# air_cylinder_control.net
KiCad netlist of a schematic drawn in Altium Designer
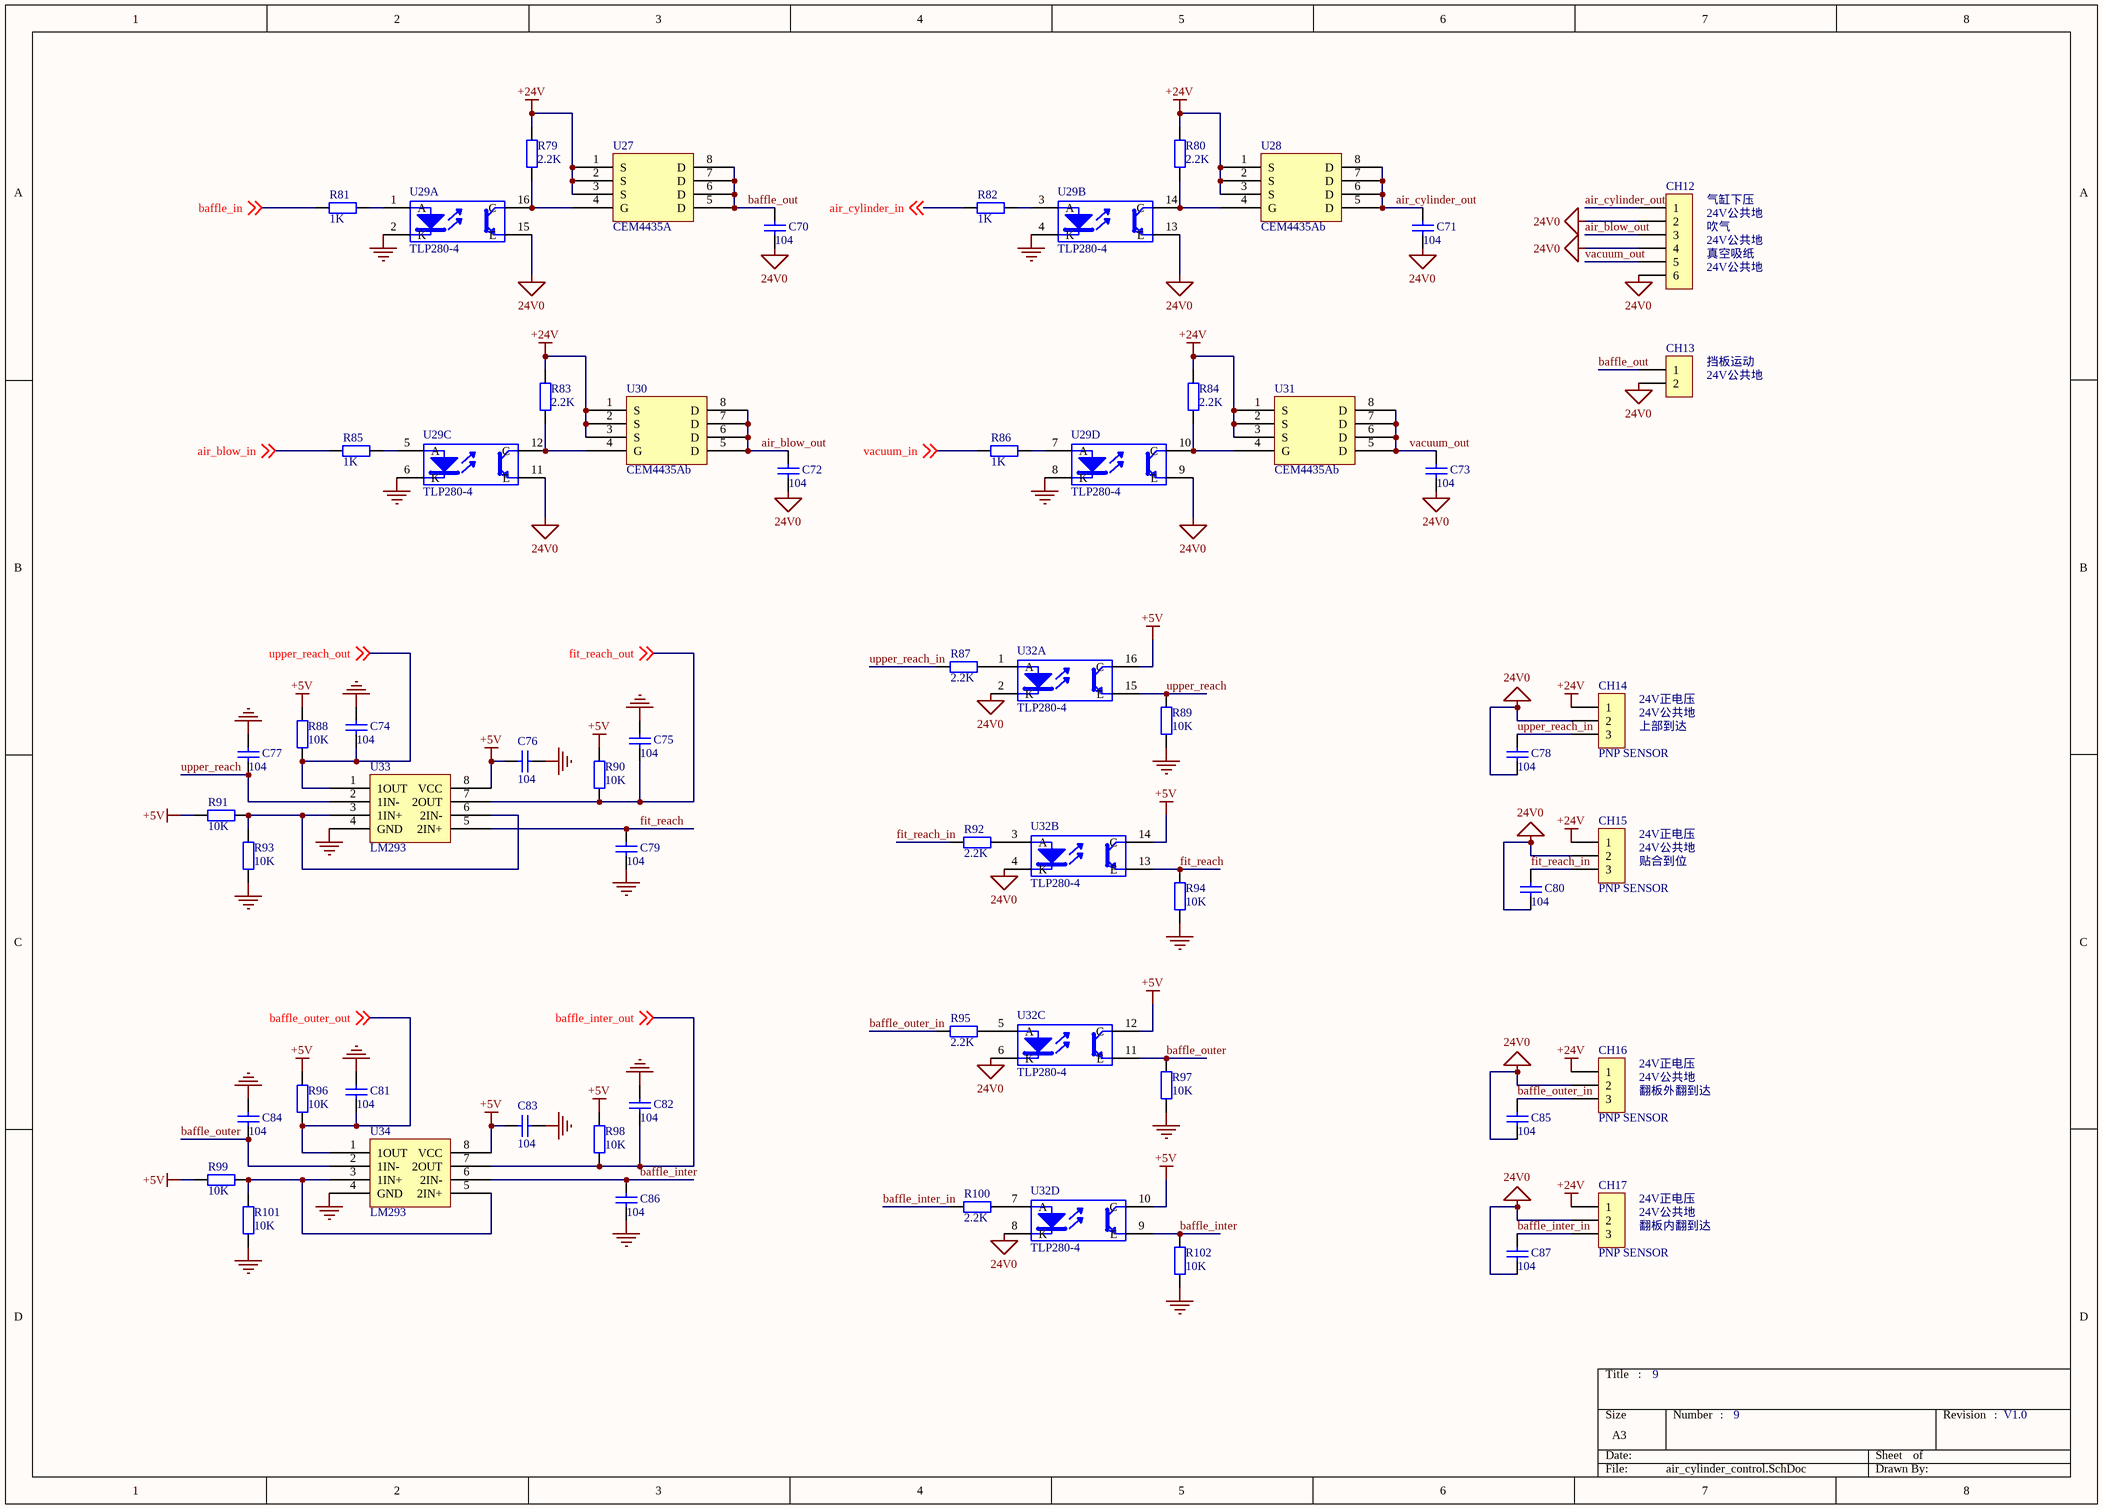
[diagram p0: air_cylinder_control.SchDoc]

(export (version "E")
  (design (tool "Eeschema 10.0.6"))
  (components
    (comp (ref "C70")
      (value "104")
      (footprint "0805")
      (description "Capacitor")
      (fields (field (name "Comment") "Capb") (field (name "PUBLISHER") "Altium Limited"))
      (libsource (lib "Miscellaneous Devices") (part "Cap"))
    )
    (comp (ref "C71")
      (value "104")
      (footprint "0805")
      (description "Capacitor")
      (fields (field (name "Comment") "Capb") (field (name "PUBLISHER") "Altium Limited"))
      (libsource (lib "Miscellaneous Devices") (part "Cap"))
    )
    (comp (ref "C72")
      (value "104")
      (footprint "0805")
      (description "Capacitor")
      (fields (field (name "Comment") "Capb") (field (name "PUBLISHER") "Altium Limited"))
      (libsource (lib "Miscellaneous Devices") (part "Cap"))
    )
    (comp (ref "C73")
      (value "104")
      (footprint "0805")
      (description "Capacitor")
      (fields (field (name "Comment") "Capb") (field (name "PUBLISHER") "Altium Limited"))
      (libsource (lib "Miscellaneous Devices") (part "Cap"))
    )
    (comp (ref "C74")
      (value "104")
      (footprint "0805")
      (description "Capacitor")
      (fields (field (name "Comment") "Cap") (field (name "PUBLISHER") "Altium Limited"))
      (libsource (lib "Miscellaneous Devices") (part "Cap"))
    )
    (comp (ref "C75")
      (value "104")
      (footprint "0805")
      (description "Capacitor")
      (fields (field (name "Comment") "Cap") (field (name "PUBLISHER") "Altium Limited"))
      (libsource (lib "Miscellaneous Devices") (part "Cap"))
    )
    (comp (ref "C76")
      (value "104")
      (footprint "0805")
      (description "Capacitor")
      (fields (field (name "Comment") "Cap") (field (name "PUBLISHER") "Altium Limited"))
      (libsource (lib "Miscellaneous Devices") (part "Cap"))
    )
    (comp (ref "C77")
      (value "104")
      (footprint "0805")
      (description "Capacitor")
      (fields (field (name "Comment") "Cap") (field (name "PUBLISHER") "Altium Limited"))
      (libsource (lib "Miscellaneous Devices") (part "Cap"))
    )
    (comp (ref "C78")
      (value "104")
      (footprint "0805")
      (description "Capacitor")
      (fields (field (name "Comment") "Capb") (field (name "PUBLISHER") "Altium Limited"))
      (libsource (lib "Miscellaneous Devices") (part "Cap"))
    )
    (comp (ref "C79")
      (value "104")
      (footprint "0805")
      (description "Capacitor")
      (fields (field (name "Comment") "Cap") (field (name "PUBLISHER") "Altium Limited"))
      (libsource (lib "Miscellaneous Devices") (part "Cap"))
    )
    (comp (ref "C80")
      (value "104")
      (footprint "0805")
      (description "Capacitor")
      (fields (field (name "Comment") "Capb") (field (name "PUBLISHER") "Altium Limited"))
      (libsource (lib "Miscellaneous Devices") (part "Cap"))
    )
    (comp (ref "C81")
      (value "104")
      (footprint "0805")
      (description "Capacitor")
      (fields (field (name "Comment") "Cap") (field (name "PUBLISHER") "Altium Limited"))
      (libsource (lib "Miscellaneous Devices") (part "Cap"))
    )
    (comp (ref "C82")
      (value "104")
      (footprint "0805")
      (description "Capacitor")
      (fields (field (name "Comment") "Cap") (field (name "PUBLISHER") "Altium Limited"))
      (libsource (lib "Miscellaneous Devices") (part "Cap"))
    )
    (comp (ref "C83")
      (value "104")
      (footprint "0805")
      (description "Capacitor")
      (fields (field (name "Comment") "Cap") (field (name "PUBLISHER") "Altium Limited"))
      (libsource (lib "Miscellaneous Devices") (part "Cap"))
    )
    (comp (ref "C84")
      (value "104")
      (footprint "0805")
      (description "Capacitor")
      (fields (field (name "Comment") "Cap") (field (name "PUBLISHER") "Altium Limited"))
      (libsource (lib "Miscellaneous Devices") (part "Cap"))
    )
    (comp (ref "C85")
      (value "104")
      (footprint "0805")
      (description "Capacitor")
      (fields (field (name "Comment") "Capb") (field (name "PUBLISHER") "Altium Limited"))
      (libsource (lib "Miscellaneous Devices") (part "Cap"))
    )
    (comp (ref "C86")
      (value "104")
      (footprint "0805")
      (description "Capacitor")
      (fields (field (name "Comment") "Cap") (field (name "PUBLISHER") "Altium Limited"))
      (libsource (lib "Miscellaneous Devices") (part "Cap"))
    )
    (comp (ref "C87")
      (value "104")
      (footprint "0805")
      (description "Capacitor")
      (fields (field (name "Comment") "Capb") (field (name "PUBLISHER") "Altium Limited"))
      (libsource (lib "Miscellaneous Devices") (part "Cap"))
    )
    (comp (ref "CH12")
      (value "HEADER1X6")
      (footprint "CH3.96-6PIN")
      (libsource (lib "myIntegrated_Library1") (part "HEADER1X6"))
    )
    (comp (ref "CH13")
      (value "HEADER1X2")
      (footprint "CH3.96-2PIN")
      (libsource (lib "myIntegrated_Library1") (part "HEADER1X2"))
    )
    (comp (ref "CH14")
      (value "HEADER1X3")
      (footprint "CH3.96-3PIN")
      (fields (field (name "ALTIUM_UNNAMED_1") "PNP SENSOR"))
      (libsource (lib "myIntegrated_Library1") (part "HEADER1X3"))
    )
    (comp (ref "CH15")
      (value "HEADER1X3")
      (footprint "CH3.96-3PIN")
      (fields (field (name "ALTIUM_UNNAMED_1") "PNP SENSOR"))
      (libsource (lib "myIntegrated_Library1") (part "HEADER1X3"))
    )
    (comp (ref "CH16")
      (value "HEADER1X3")
      (footprint "CH3.96-3PIN")
      (fields (field (name "ALTIUM_UNNAMED_1") "PNP SENSOR"))
      (libsource (lib "myIntegrated_Library1") (part "HEADER1X3"))
    )
    (comp (ref "CH17")
      (value "HEADER1X3")
      (footprint "CH3.96-3PIN")
      (fields (field (name "ALTIUM_UNNAMED_1") "PNP SENSOR"))
      (libsource (lib "myIntegrated_Library1") (part "HEADER1X3"))
    )
    (comp (ref "R79")
      (value "2.2K")
      (footprint "0805")
      (description "Resistor")
      (fields (field (name "Comment") "Res2") (field (name "PUBLISHER") "Altium Limited"))
      (libsource (lib "") (part "Res2_2"))
    )
    (comp (ref "R80")
      (value "2.2K")
      (footprint "0805")
      (description "Resistor")
      (fields (field (name "Comment") "Res2") (field (name "PUBLISHER") "Altium Limited"))
      (libsource (lib "") (part "Res2_2"))
    )
    (comp (ref "R81")
      (value "1K")
      (footprint "0805")
      (description "Resistor")
      (fields (field (name "Comment") "Res2") (field (name "PUBLISHER") "Altium Limited"))
      (libsource (lib "") (part "Res2_1"))
    )
    (comp (ref "R82")
      (value "1K")
      (footprint "0805")
      (description "Resistor")
      (fields (field (name "Comment") "Res2") (field (name "PUBLISHER") "Altium Limited"))
      (libsource (lib "") (part "Res2_1"))
    )
    (comp (ref "R83")
      (value "2.2K")
      (footprint "0805")
      (description "Resistor")
      (fields (field (name "Comment") "Res2") (field (name "PUBLISHER") "Altium Limited"))
      (libsource (lib "") (part "Res2_2"))
    )
    (comp (ref "R84")
      (value "2.2K")
      (footprint "0805")
      (description "Resistor")
      (fields (field (name "Comment") "Res2") (field (name "PUBLISHER") "Altium Limited"))
      (libsource (lib "") (part "Res2_2"))
    )
    (comp (ref "R85")
      (value "1K")
      (footprint "0805")
      (description "Resistor")
      (fields (field (name "Comment") "Res2") (field (name "PUBLISHER") "Altium Limited"))
      (libsource (lib "") (part "Res2_1"))
    )
    (comp (ref "R86")
      (value "1K")
      (footprint "0805")
      (description "Resistor")
      (fields (field (name "Comment") "Res2") (field (name "PUBLISHER") "Altium Limited"))
      (libsource (lib "") (part "Res2_1"))
    )
    (comp (ref "R87")
      (value "2.2K")
      (footprint "0805")
      (description "Resistor")
      (fields (field (name "Comment") "Res2") (field (name "PUBLISHER") "Altium Limited"))
      (libsource (lib "") (part "Res2_1"))
    )
    (comp (ref "R88")
      (value "10K")
      (footprint "0805")
      (description "Resistor")
      (fields (field (name "Comment") "Res2") (field (name "PUBLISHER") "Altium Limited"))
      (libsource (lib "Miscellaneous Devices") (part "Res2"))
    )
    (comp (ref "R89")
      (value "10K")
      (footprint "0805")
      (description "Resistor")
      (fields (field (name "Comment") "Res2") (field (name "PUBLISHER") "Altium Limited"))
      (libsource (lib "Miscellaneous Devices") (part "Res2"))
    )
    (comp (ref "R90")
      (value "10K")
      (footprint "0805")
      (description "Resistor")
      (fields (field (name "Comment") "Res2") (field (name "PUBLISHER") "Altium Limited"))
      (libsource (lib "Miscellaneous Devices") (part "Res2"))
    )
    (comp (ref "R91")
      (value "10K")
      (footprint "0805")
      (description "Resistor")
      (fields (field (name "Comment") "Res2") (field (name "PUBLISHER") "Altium Limited"))
      (libsource (lib "") (part "Res2_3"))
    )
    (comp (ref "R92")
      (value "2.2K")
      (footprint "0805")
      (description "Resistor")
      (fields (field (name "Comment") "Res2") (field (name "PUBLISHER") "Altium Limited"))
      (libsource (lib "") (part "Res2_1"))
    )
    (comp (ref "R93")
      (value "10K")
      (footprint "0805")
      (description "Resistor")
      (fields (field (name "Comment") "Res2") (field (name "PUBLISHER") "Altium Limited"))
      (libsource (lib "Miscellaneous Devices") (part "Res2"))
    )
    (comp (ref "R94")
      (value "10K")
      (footprint "0805")
      (description "Resistor")
      (fields (field (name "Comment") "Res2") (field (name "PUBLISHER") "Altium Limited"))
      (libsource (lib "Miscellaneous Devices") (part "Res2"))
    )
    (comp (ref "R95")
      (value "2.2K")
      (footprint "0805")
      (description "Resistor")
      (fields (field (name "Comment") "Res2") (field (name "PUBLISHER") "Altium Limited"))
      (libsource (lib "") (part "Res2_1"))
    )
    (comp (ref "R96")
      (value "10K")
      (footprint "0805")
      (description "Resistor")
      (fields (field (name "Comment") "Res2") (field (name "PUBLISHER") "Altium Limited"))
      (libsource (lib "Miscellaneous Devices") (part "Res2"))
    )
    (comp (ref "R97")
      (value "10K")
      (footprint "0805")
      (description "Resistor")
      (fields (field (name "Comment") "Res2") (field (name "PUBLISHER") "Altium Limited"))
      (libsource (lib "Miscellaneous Devices") (part "Res2"))
    )
    (comp (ref "R98")
      (value "10K")
      (footprint "0805")
      (description "Resistor")
      (fields (field (name "Comment") "Res2") (field (name "PUBLISHER") "Altium Limited"))
      (libsource (lib "Miscellaneous Devices") (part "Res2"))
    )
    (comp (ref "R99")
      (value "10K")
      (footprint "0805")
      (description "Resistor")
      (fields (field (name "Comment") "Res2") (field (name "PUBLISHER") "Altium Limited"))
      (libsource (lib "") (part "Res2_3"))
    )
    (comp (ref "R100")
      (value "2.2K")
      (footprint "0805")
      (description "Resistor")
      (fields (field (name "Comment") "Res2") (field (name "PUBLISHER") "Altium Limited"))
      (libsource (lib "") (part "Res2_1"))
    )
    (comp (ref "R101")
      (value "10K")
      (footprint "0805")
      (description "Resistor")
      (fields (field (name "Comment") "Res2") (field (name "PUBLISHER") "Altium Limited"))
      (libsource (lib "Miscellaneous Devices") (part "Res2"))
    )
    (comp (ref "R102")
      (value "10K")
      (footprint "0805")
      (description "Resistor")
      (fields (field (name "Comment") "Res2") (field (name "PUBLISHER") "Altium Limited"))
      (libsource (lib "Miscellaneous Devices") (part "Res2"))
    )
    (comp (ref "U27")
      (value "CEM4435A")
      (footprint "SOP8-OP27")
      (libsource (lib "myIntegrated_Library1") (part "CEM4435A"))
    )
    (comp (ref "U28")
      (value "CEM4435Ab")
      (footprint "SOP8-OP27")
      (libsource (lib "myIntegrated_Library1") (part "CEM4435A"))
    )
    (comp (ref "U29") (value "TLP280-4") (footprint "SO16") (libsource (lib "WH V20") (part "TLP521-4")))
    (comp (ref "U30")
      (value "CEM4435Ab")
      (footprint "SOP8-OP27")
      (libsource (lib "myIntegrated_Library1") (part "CEM4435A"))
    )
    (comp (ref "U31")
      (value "CEM4435Ab")
      (footprint "SOP8-OP27")
      (libsource (lib "myIntegrated_Library1") (part "CEM4435A"))
    )
    (comp (ref "U32") (value "TLP280-4") (footprint "SO16") (libsource (lib "WH V20") (part "TLP521-4")))
    (comp (ref "U33")
      (value "LM293")
      (footprint "SOP8-OP27")
      (libsource (lib "myIntegrated_Library1") (part "LM293"))
    )
    (comp (ref "U34")
      (value "LM293")
      (footprint "SOP8-OP27")
      (libsource (lib "myIntegrated_Library1") (part "LM293"))
    )
  )
  (nets
    (net (code "1") (name "+5V") (class "Default")
      (node (ref "C76") (pin "2") (pinfunction "2_2") (pintype "passive"))
      (node (ref "C83") (pin "2") (pinfunction "2_2") (pintype "passive"))
      (node (ref "R88") (pin "2") (pinfunction "2_2") (pintype "passive"))
      (node (ref "R90") (pin "2") (pinfunction "2_2") (pintype "passive"))
      (node (ref "R91") (pin "2") (pinfunction "2_2") (pintype "passive"))
      (node (ref "R96") (pin "2") (pinfunction "2_2") (pintype "passive"))
      (node (ref "R98") (pin "2") (pinfunction "2_2") (pintype "passive"))
      (node (ref "R99") (pin "2") (pinfunction "2_2") (pintype "passive"))
      (node (ref "U32") (pin "10") (pinfunction "C_10") (pintype "passive"))
      (node (ref "U32") (pin "12") (pinfunction "C_12") (pintype "passive"))
      (node (ref "U32") (pin "14") (pinfunction "C_14") (pintype "passive"))
      (node (ref "U32") (pin "16") (pinfunction "C_16") (pintype "passive"))
      (node (ref "U33") (pin "8") (pinfunction "VCC_8") (pintype "passive"))
      (node (ref "U34") (pin "8") (pinfunction "VCC_8") (pintype "passive"))
    )
    (net (code "2") (name "+24V") (class "Default")
      (node (ref "CH14") (pin "1") (pinfunction "1_1") (pintype "passive"))
      (node (ref "CH15") (pin "1") (pinfunction "1_1") (pintype "passive"))
      (node (ref "CH16") (pin "1") (pinfunction "1_1") (pintype "passive"))
      (node (ref "CH17") (pin "1") (pinfunction "1_1") (pintype "passive"))
      (node (ref "R79") (pin "1") (pinfunction "1_1") (pintype "passive"))
      (node (ref "R80") (pin "1") (pinfunction "1_1") (pintype "passive"))
      (node (ref "R83") (pin "1") (pinfunction "1_1") (pintype "passive"))
      (node (ref "R84") (pin "1") (pinfunction "1_1") (pintype "passive"))
      (node (ref "U27") (pin "1") (pinfunction "S_1") (pintype "passive"))
      (node (ref "U27") (pin "2") (pinfunction "S_2") (pintype "passive"))
      (node (ref "U27") (pin "3") (pinfunction "S_3") (pintype "passive"))
      (node (ref "U28") (pin "1") (pinfunction "S_1") (pintype "passive"))
      (node (ref "U28") (pin "2") (pinfunction "S_2") (pintype "passive"))
      (node (ref "U28") (pin "3") (pinfunction "S_3") (pintype "passive"))
      (node (ref "U30") (pin "1") (pinfunction "S_1") (pintype "passive"))
      (node (ref "U30") (pin "2") (pinfunction "S_2") (pintype "passive"))
      (node (ref "U30") (pin "3") (pinfunction "S_3") (pintype "passive"))
      (node (ref "U31") (pin "1") (pinfunction "S_1") (pintype "passive"))
      (node (ref "U31") (pin "2") (pinfunction "S_2") (pintype "passive"))
      (node (ref "U31") (pin "3") (pinfunction "S_3") (pintype "passive"))
    )
    (net (code "3") (name "/air_blow_out") (class "Default")
      (node (ref "C72") (pin "2") (pinfunction "2_2") (pintype "passive"))
      (node (ref "CH12") (pin "3") (pinfunction "3_3") (pintype "passive"))
      (node (ref "U30") (pin "5") (pinfunction "D_5") (pintype "passive"))
      (node (ref "U30") (pin "6") (pinfunction "D_6") (pintype "passive"))
      (node (ref "U30") (pin "7") (pinfunction "D_7") (pintype "passive"))
      (node (ref "U30") (pin "8") (pinfunction "D_8") (pintype "passive"))
    )
    (net (code "4") (name "/air_cylinder_out") (class "Default")
      (node (ref "C71") (pin "2") (pinfunction "2_2") (pintype "passive"))
      (node (ref "CH12") (pin "1") (pinfunction "1_1") (pintype "passive"))
      (node (ref "U28") (pin "5") (pinfunction "D_5") (pintype "passive"))
      (node (ref "U28") (pin "6") (pinfunction "D_6") (pintype "passive"))
      (node (ref "U28") (pin "7") (pinfunction "D_7") (pintype "passive"))
      (node (ref "U28") (pin "8") (pinfunction "D_8") (pintype "passive"))
    )
    (net (code "5") (name "/baffle_inter") (class "Default")
      (node (ref "C86") (pin "2") (pinfunction "2_2") (pintype "passive"))
      (node (ref "R102") (pin "2") (pinfunction "2_2") (pintype "passive"))
      (node (ref "U32") (pin "9") (pinfunction "E_9") (pintype "passive"))
      (node (ref "U34") (pin "6") (pinfunction "2IN-_6") (pintype "passive"))
    )
    (net (code "6") (name "/baffle_inter_in") (class "Default")
      (node (ref "C87") (pin "2") (pinfunction "2_2") (pintype "passive"))
      (node (ref "CH17") (pin "3") (pinfunction "3_3") (pintype "passive"))
      (node (ref "R100") (pin "1") (pinfunction "1_1") (pintype "passive"))
    )
    (net (code "7") (name "/baffle_out") (class "Default")
      (node (ref "C70") (pin "2") (pinfunction "2_2") (pintype "passive"))
      (node (ref "CH13") (pin "1") (pinfunction "1_1") (pintype "passive"))
      (node (ref "U27") (pin "5") (pinfunction "D_5") (pintype "passive"))
      (node (ref "U27") (pin "6") (pinfunction "D_6") (pintype "passive"))
      (node (ref "U27") (pin "7") (pinfunction "D_7") (pintype "passive"))
      (node (ref "U27") (pin "8") (pinfunction "D_8") (pintype "passive"))
    )
    (net (code "8") (name "/baffle_outer") (class "Default")
      (node (ref "C84") (pin "1") (pinfunction "1_1") (pintype "passive"))
      (node (ref "R97") (pin "2") (pinfunction "2_2") (pintype "passive"))
      (node (ref "U32") (pin "11") (pinfunction "E_11") (pintype "passive"))
      (node (ref "U34") (pin "2") (pinfunction "1IN-_2") (pintype "passive"))
    )
    (net (code "9") (name "/baffle_outer_in") (class "Default")
      (node (ref "C85") (pin "2") (pinfunction "2_2") (pintype "passive"))
      (node (ref "CH16") (pin "3") (pinfunction "3_3") (pintype "passive"))
      (node (ref "R95") (pin "1") (pinfunction "1_1") (pintype "passive"))
    )
    (net (code "10") (name "/fit_reach") (class "Default")
      (node (ref "C79") (pin "2") (pinfunction "2_2") (pintype "passive"))
      (node (ref "R94") (pin "2") (pinfunction "2_2") (pintype "passive"))
      (node (ref "U32") (pin "13") (pinfunction "E_13") (pintype "passive"))
      (node (ref "U33") (pin "5") (pinfunction "2IN+_5") (pintype "passive"))
    )
    (net (code "11") (name "/fit_reach_in") (class "Default")
      (node (ref "C80") (pin "2") (pinfunction "2_2") (pintype "passive"))
      (node (ref "CH15") (pin "3") (pinfunction "3_3") (pintype "passive"))
      (node (ref "R92") (pin "1") (pinfunction "1_1") (pintype "passive"))
    )
    (net (code "12") (name "/upper_reach") (class "Default")
      (node (ref "C77") (pin "1") (pinfunction "1_1") (pintype "passive"))
      (node (ref "R89") (pin "2") (pinfunction "2_2") (pintype "passive"))
      (node (ref "U32") (pin "15") (pinfunction "E_15") (pintype "passive"))
      (node (ref "U33") (pin "2") (pinfunction "1IN-_2") (pintype "passive"))
    )
    (net (code "13") (name "/upper_reach_in") (class "Default")
      (node (ref "C78") (pin "2") (pinfunction "2_2") (pintype "passive"))
      (node (ref "CH14") (pin "3") (pinfunction "3_3") (pintype "passive"))
      (node (ref "R87") (pin "1") (pinfunction "1_1") (pintype "passive"))
    )
    (net (code "14") (name "/vacuum_out") (class "Default")
      (node (ref "C73") (pin "2") (pinfunction "2_2") (pintype "passive"))
      (node (ref "CH12") (pin "5") (pinfunction "5_5") (pintype "passive"))
      (node (ref "U31") (pin "5") (pinfunction "D_5") (pintype "passive"))
      (node (ref "U31") (pin "6") (pinfunction "D_6") (pintype "passive"))
      (node (ref "U31") (pin "7") (pinfunction "D_7") (pintype "passive"))
      (node (ref "U31") (pin "8") (pinfunction "D_8") (pintype "passive"))
    )
    (net (code "15") (name "24V0") (class "Default")
      (node (ref "C70") (pin "1") (pinfunction "1_1") (pintype "passive"))
      (node (ref "C71") (pin "1") (pinfunction "1_1") (pintype "passive"))
      (node (ref "C72") (pin "1") (pinfunction "1_1") (pintype "passive"))
      (node (ref "C73") (pin "1") (pinfunction "1_1") (pintype "passive"))
      (node (ref "C78") (pin "1") (pinfunction "1_1") (pintype "passive"))
      (node (ref "C80") (pin "1") (pinfunction "1_1") (pintype "passive"))
      (node (ref "C85") (pin "1") (pinfunction "1_1") (pintype "passive"))
      (node (ref "C87") (pin "1") (pinfunction "1_1") (pintype "passive"))
      (node (ref "CH12") (pin "2") (pinfunction "2_2") (pintype "passive"))
      (node (ref "CH12") (pin "4") (pinfunction "4_4") (pintype "passive"))
      (node (ref "CH12") (pin "6") (pinfunction "6_6") (pintype "passive"))
      (node (ref "CH13") (pin "2") (pinfunction "2_2") (pintype "passive"))
      (node (ref "CH14") (pin "2") (pinfunction "2_2") (pintype "passive"))
      (node (ref "CH15") (pin "2") (pinfunction "2_2") (pintype "passive"))
      (node (ref "CH16") (pin "2") (pinfunction "2_2") (pintype "passive"))
      (node (ref "CH17") (pin "2") (pinfunction "2_2") (pintype "passive"))
      (node (ref "U29") (pin "11") (pinfunction "E_11") (pintype "passive"))
      (node (ref "U29") (pin "13") (pinfunction "E_13") (pintype "passive"))
      (node (ref "U29") (pin "15") (pinfunction "E_15") (pintype "passive"))
      (node (ref "U29") (pin "9") (pinfunction "E_9") (pintype "passive"))
      (node (ref "U32") (pin "2") (pinfunction "K_2") (pintype "passive"))
      (node (ref "U32") (pin "4") (pinfunction "K_4") (pintype "passive"))
      (node (ref "U32") (pin "6") (pinfunction "K_6") (pintype "passive"))
      (node (ref "U32") (pin "8") (pinfunction "K_8") (pintype "passive"))
    )
    (net (code "16") (name "GND") (class "Default")
      (node (ref "C74") (pin "2") (pinfunction "2_2") (pintype "passive"))
      (node (ref "C75") (pin "2") (pinfunction "2_2") (pintype "passive"))
      (node (ref "C76") (pin "1") (pinfunction "1_1") (pintype "passive"))
      (node (ref "C77") (pin "2") (pinfunction "2_2") (pintype "passive"))
      (node (ref "C79") (pin "1") (pinfunction "1_1") (pintype "passive"))
      (node (ref "C81") (pin "2") (pinfunction "2_2") (pintype "passive"))
      (node (ref "C82") (pin "2") (pinfunction "2_2") (pintype "passive"))
      (node (ref "C83") (pin "1") (pinfunction "1_1") (pintype "passive"))
      (node (ref "C84") (pin "2") (pinfunction "2_2") (pintype "passive"))
      (node (ref "C86") (pin "1") (pinfunction "1_1") (pintype "passive"))
      (node (ref "R101") (pin "1") (pinfunction "1_1") (pintype "passive"))
      (node (ref "R102") (pin "1") (pinfunction "1_1") (pintype "passive"))
      (node (ref "R89") (pin "1") (pinfunction "1_1") (pintype "passive"))
      (node (ref "R93") (pin "1") (pinfunction "1_1") (pintype "passive"))
      (node (ref "R94") (pin "1") (pinfunction "1_1") (pintype "passive"))
      (node (ref "R97") (pin "1") (pinfunction "1_1") (pintype "passive"))
      (node (ref "U29") (pin "2") (pinfunction "K_2") (pintype "passive"))
      (node (ref "U29") (pin "4") (pinfunction "K_4") (pintype "passive"))
      (node (ref "U29") (pin "6") (pinfunction "K_6") (pintype "passive"))
      (node (ref "U29") (pin "8") (pinfunction "K_8") (pintype "passive"))
      (node (ref "U33") (pin "4") (pinfunction "GND_4") (pintype "passive"))
      (node (ref "U34") (pin "4") (pinfunction "GND_4") (pintype "passive"))
    )
    (net (code "17") (name "Net-(U27-G)") (class "Default")
      (node (ref "R79") (pin "2") (pinfunction "2_2") (pintype "passive"))
      (node (ref "U27") (pin "4") (pinfunction "G_4") (pintype "passive"))
      (node (ref "U29") (pin "16") (pinfunction "C_16") (pintype "passive"))
    )
    (net (code "18") (name "Net-(U28-G)") (class "Default")
      (node (ref "R80") (pin "2") (pinfunction "2_2") (pintype "passive"))
      (node (ref "U28") (pin "4") (pinfunction "G_4") (pintype "passive"))
      (node (ref "U29") (pin "14") (pinfunction "C_14") (pintype "passive"))
    )
    (net (code "19") (name "Net-(U29A-A)") (class "Default")
      (node (ref "R81") (pin "2") (pinfunction "2_2") (pintype "passive"))
      (node (ref "U29") (pin "1") (pinfunction "A_1") (pintype "passive"))
    )
    (net (code "20") (name "Net-(U29B-A)") (class "Default")
      (node (ref "R82") (pin "2") (pinfunction "2_2") (pintype "passive"))
      (node (ref "U29") (pin "3") (pinfunction "A_3") (pintype "passive"))
    )
    (net (code "21") (name "Net-(U29C-A)") (class "Default")
      (node (ref "R85") (pin "2") (pinfunction "2_2") (pintype "passive"))
      (node (ref "U29") (pin "5") (pinfunction "A_5") (pintype "passive"))
    )
    (net (code "22") (name "Net-(U29C-C)") (class "Default")
      (node (ref "R83") (pin "2") (pinfunction "2_2") (pintype "passive"))
      (node (ref "U29") (pin "12") (pinfunction "C_12") (pintype "passive"))
      (node (ref "U30") (pin "4") (pinfunction "G_4") (pintype "passive"))
    )
    (net (code "23") (name "Net-(U29D-A)") (class "Default")
      (node (ref "R86") (pin "2") (pinfunction "2_2") (pintype "passive"))
      (node (ref "U29") (pin "7") (pinfunction "A_7") (pintype "passive"))
    )
    (net (code "24") (name "Net-(U29D-C)") (class "Default")
      (node (ref "R84") (pin "2") (pinfunction "2_2") (pintype "passive"))
      (node (ref "U29") (pin "10") (pinfunction "C_10") (pintype "passive"))
      (node (ref "U31") (pin "4") (pinfunction "G_4") (pintype "passive"))
    )
    (net (code "25") (name "Net-(U32A-A)") (class "Default")
      (node (ref "R87") (pin "2") (pinfunction "2_2") (pintype "passive"))
      (node (ref "U32") (pin "1") (pinfunction "A_1") (pintype "passive"))
    )
    (net (code "26") (name "Net-(U32B-A)") (class "Default")
      (node (ref "R92") (pin "2") (pinfunction "2_2") (pintype "passive"))
      (node (ref "U32") (pin "3") (pinfunction "A_3") (pintype "passive"))
    )
    (net (code "27") (name "Net-(U32C-A)") (class "Default")
      (node (ref "R95") (pin "2") (pinfunction "2_2") (pintype "passive"))
      (node (ref "U32") (pin "5") (pinfunction "A_5") (pintype "passive"))
    )
    (net (code "28") (name "Net-(U32D-A)") (class "Default")
      (node (ref "R100") (pin "2") (pinfunction "2_2") (pintype "passive"))
      (node (ref "U32") (pin "7") (pinfunction "A_7") (pintype "passive"))
    )
    (net (code "29") (name "Net-(U33-1IN+)") (class "Default")
      (node (ref "R91") (pin "1") (pinfunction "1_1") (pintype "passive"))
      (node (ref "R93") (pin "2") (pinfunction "2_2") (pintype "passive"))
      (node (ref "U33") (pin "3") (pinfunction "1IN+_3") (pintype "passive"))
      (node (ref "U33") (pin "6") (pinfunction "2IN-_6") (pintype "passive"))
    )
    (net (code "30") (name "Net-(U34-1IN+)") (class "Default")
      (node (ref "R101") (pin "2") (pinfunction "2_2") (pintype "passive"))
      (node (ref "R99") (pin "1") (pinfunction "1_1") (pintype "passive"))
      (node (ref "U34") (pin "3") (pinfunction "1IN+_3") (pintype "passive"))
      (node (ref "U34") (pin "5") (pinfunction "2IN+_5") (pintype "passive"))
    )
    (net (code "31") (name "air_blow_in") (class "Default")
      (node (ref "R85") (pin "1") (pinfunction "1_1") (pintype "passive"))
    )
    (net (code "32") (name "air_cylinder_in") (class "Default")
      (node (ref "R82") (pin "1") (pinfunction "1_1") (pintype "passive"))
    )
    (net (code "33") (name "baffle_in") (class "Default")
      (node (ref "R81") (pin "1") (pinfunction "1_1") (pintype "passive"))
    )
    (net (code "34") (name "baffle_inter_out") (class "Default")
      (node (ref "C82") (pin "1") (pinfunction "1_1") (pintype "passive"))
      (node (ref "R98") (pin "1") (pinfunction "1_1") (pintype "passive"))
      (node (ref "U34") (pin "7") (pinfunction "2OUT_7") (pintype "passive"))
    )
    (net (code "35") (name "baffle_outer_out") (class "Default")
      (node (ref "C81") (pin "1") (pinfunction "1_1") (pintype "passive"))
      (node (ref "R96") (pin "1") (pinfunction "1_1") (pintype "passive"))
      (node (ref "U34") (pin "1") (pinfunction "1OUT_1") (pintype "passive"))
    )
    (net (code "36") (name "fit_reach_out") (class "Default")
      (node (ref "C75") (pin "1") (pinfunction "1_1") (pintype "passive"))
      (node (ref "R90") (pin "1") (pinfunction "1_1") (pintype "passive"))
      (node (ref "U33") (pin "7") (pinfunction "2OUT_7") (pintype "passive"))
    )
    (net (code "37") (name "upper_reach_out") (class "Default")
      (node (ref "C74") (pin "1") (pinfunction "1_1") (pintype "passive"))
      (node (ref "R88") (pin "1") (pinfunction "1_1") (pintype "passive"))
      (node (ref "U33") (pin "1") (pinfunction "1OUT_1") (pintype "passive"))
    )
    (net (code "38") (name "vacuum_in") (class "Default")
      (node (ref "R86") (pin "1") (pinfunction "1_1") (pintype "passive"))
    )
  )
)
